# SPI_Digital_Outputs.net
KiCad netlist of a schematic drawn in Altium Designer
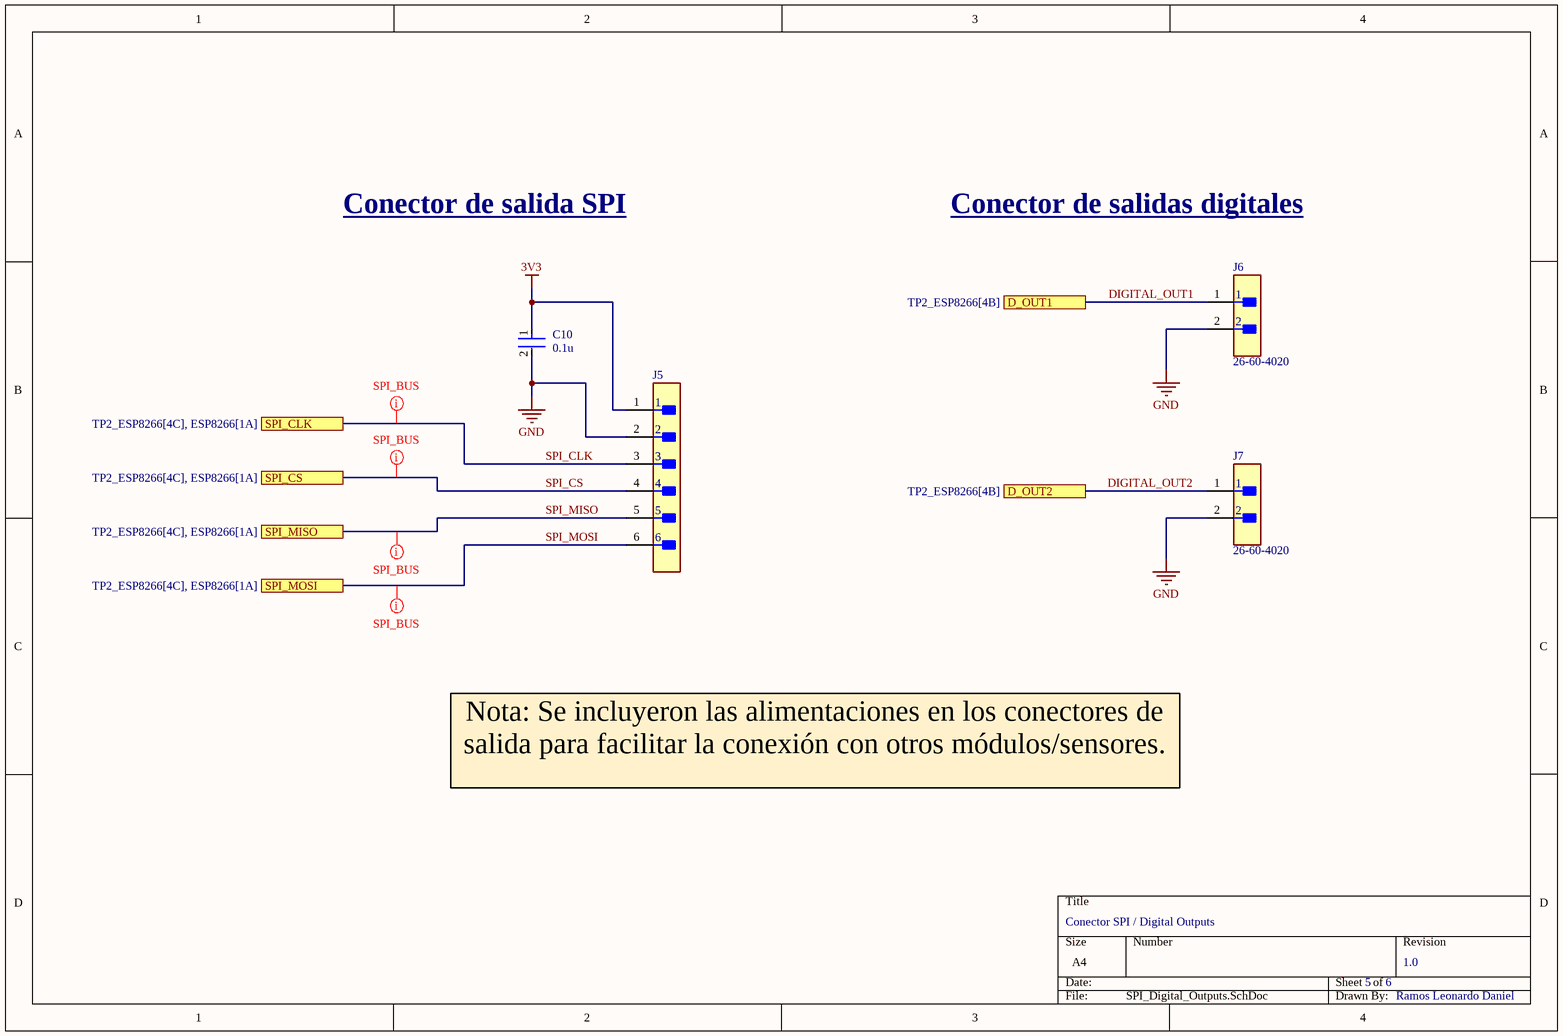
[diagram p0: SPI_Digital_Outputs.SchDoc]

(export (version "E")
  (design (tool "Eeschema 10.0.6"))
  (components
    (comp (ref "C10")
      (value "0.1u")
      (footprint "FP-CC0805-0_85-MFG")
      (description "CAP CER 0.1UF 25V X7R 0805")
      (fields (field (name "MANUFACTURER PART NUMBER") "CC0805KRX7R8BB104") (field (name "TOLERANCE") "0.1"))
      (libsource (lib "Altium Content Vault") (part "11868f565c42a9108669ba33697ecf6"))
    )
    (comp (ref "J5")
      (value "22-27-2061")
      (footprint "FP-22-27-2061-MFG")
      (description "CONN HEADER VERT 6POS 2.54MM")
      (libsource (lib "Altium Content Vault") (part "f2cb566baf1c37ab5a3b8e90bbeafd6"))
    )
    (comp (ref "J6")
      (value "26-60-4020")
      (footprint "FP-26-60-4020-MFG")
      (description "CONN HEADER VERT 2POS 3.96MM")
      (libsource (lib "Altium Content Vault") (part "3bc925449376181038e59eaffc5286c"))
    )
    (comp (ref "J7")
      (value "26-60-4020")
      (footprint "FP-26-60-4020-MFG")
      (description "CONN HEADER VERT 2POS 3.96MM")
      (libsource (lib "Altium Content Vault") (part "3bc925449376181038e59eaffc5286c"))
    )
  )
  (nets
    (net (code "1") (name "/DIGITAL_OUT1") (class "Default")
      (node (ref "J6") (pin "1") (pinfunction "1_1") (pintype "passive"))
    )
    (net (code "2") (name "/DIGITAL_OUT2") (class "Default")
      (node (ref "J7") (pin "1") (pinfunction "1_1") (pintype "passive"))
    )
    (net (code "3") (name "/SPI_CLK") (class "Default")
      (node (ref "J5") (pin "3") (pinfunction "3_3") (pintype "passive"))
    )
    (net (code "4") (name "/SPI_CS") (class "Default")
      (node (ref "J5") (pin "4") (pinfunction "4_4") (pintype "passive"))
    )
    (net (code "5") (name "/SPI_MISO") (class "Default")
      (node (ref "J5") (pin "5") (pinfunction "5_5") (pintype "passive"))
    )
    (net (code "6") (name "/SPI_MOSI") (class "Default")
      (node (ref "J5") (pin "6") (pinfunction "6_6") (pintype "passive"))
    )
    (net (code "7") (name "3V3") (class "Default")
      (node (ref "C10") (pin "1") (pinfunction "1_1") (pintype "passive"))
      (node (ref "J5") (pin "1") (pinfunction "1_1") (pintype "passive"))
    )
    (net (code "8") (name "GND") (class "Default")
      (node (ref "C10") (pin "2") (pinfunction "2_2") (pintype "passive"))
      (node (ref "J5") (pin "2") (pinfunction "2_2") (pintype "passive"))
      (node (ref "J6") (pin "2") (pinfunction "2_2") (pintype "passive"))
      (node (ref "J7") (pin "2") (pinfunction "2_2") (pintype "passive"))
    )
  )
)
